# 7_can_rc_i2c_analog.net
KiCad netlist of a schematic drawn in Altium Designer
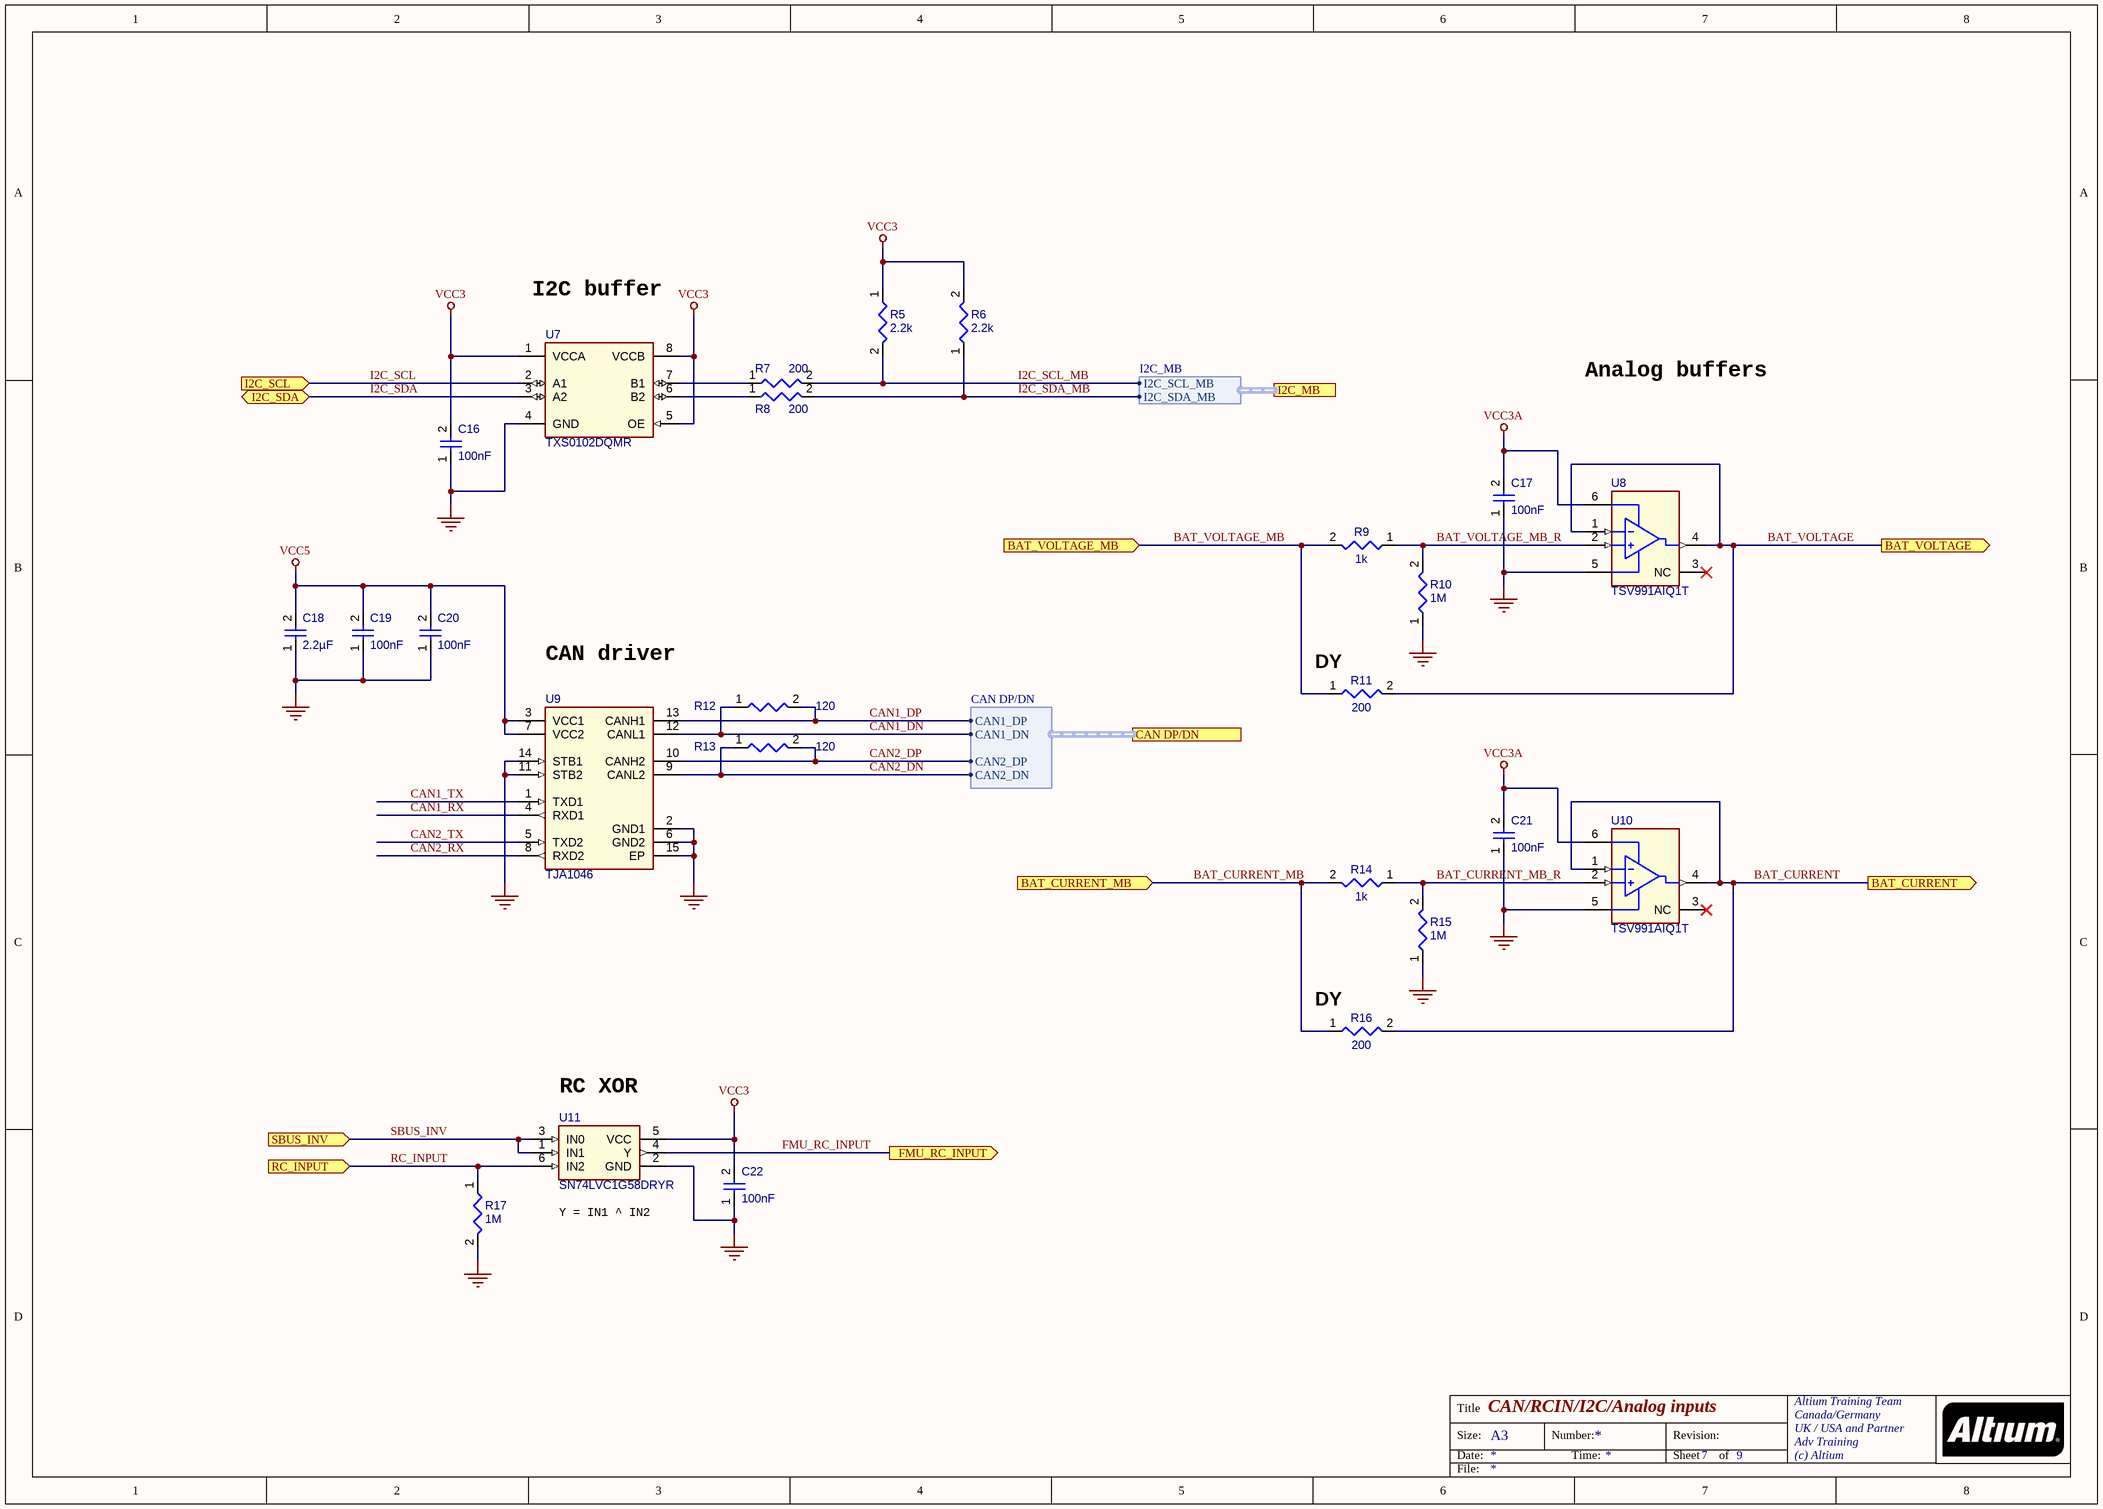
[diagram p0: 7_can_rc_i2c_analog.SchDoc]

(export (version "E")
  (design (tool "Eeschema 10.0.6"))
  (components
    (comp (ref "C16")
      (value "100nF")
      (footprint "CAPC0402(1005)60_L")
      (description "Chip Capacitor, 100nF +/-20%, 10V, 0402, Thickness 0.6 mm")
      (fields (field (name "TOLERANCE") "20%") (field (name "Comment") "Capacitor 100nF +/-20% 10V 0402"))
      (libsource (lib "<Company> Server") (part "CAP-NP-2"))
    )
    (comp (ref "C17")
      (value "100nF")
      (footprint "CAPC0402(1005)60_L")
      (description "Chip Capacitor, 100nF +/-20%, 10V, 0402, Thickness 0.6 mm")
      (fields (field (name "TOLERANCE") "20%") (field (name "Comment") "Capacitor 100nF +/-20% 10V 0402"))
      (libsource (lib "<Company> Server") (part "CAP-NP-2"))
    )
    (comp (ref "C18")
      (value "2.2µF")
      (footprint "CAPC0402(1005)60_L")
      (description "Chip Capacitor, 2,2µF +/-20%, 10V, 0402, Thickness 0.6 mm")
      (fields (field (name "TOLERANCE") "10%") (field (name "Comment") "Capacitor 2,2µF +/-20% 10V 0402"))
      (libsource (lib "<Company> Server") (part "CAP-NP-2"))
    )
    (comp (ref "C19")
      (value "100nF")
      (footprint "CAPC0402(1005)60_L")
      (description "Chip Capacitor, 100nF +/-20%, 10V, 0402, Thickness 0.6 mm")
      (fields (field (name "TOLERANCE") "20%") (field (name "Comment") "Capacitor 100nF +/-20% 10V 0402"))
      (libsource (lib "<Company> Server") (part "CAP-NP-2"))
    )
    (comp (ref "C20")
      (value "100nF")
      (footprint "CAPC0402(1005)60_L")
      (description "Chip Capacitor, 100nF +/-20%, 10V, 0402, Thickness 0.6 mm")
      (fields (field (name "TOLERANCE") "20%") (field (name "Comment") "Capacitor 100nF +/-20% 10V 0402"))
      (libsource (lib "<Company> Server") (part "CAP-NP-2"))
    )
    (comp (ref "C21")
      (value "100nF")
      (footprint "CAPC0402(1005)60_L")
      (description "Chip Capacitor, 100nF +/-20%, 10V, 0402, Thickness 0.6 mm")
      (fields (field (name "TOLERANCE") "20%") (field (name "Comment") "Capacitor 100nF +/-20% 10V 0402"))
      (libsource (lib "<Company> Server") (part "CAP-NP-2"))
    )
    (comp (ref "C22")
      (value "100nF")
      (footprint "CAPC0402(1005)60_L")
      (description "Chip Capacitor, 100nF +/-20%, 10V, 0402, Thickness 0.6 mm")
      (fields (field (name "TOLERANCE") "20%") (field (name "Comment") "Capacitor 100nF +/-20% 10V 0402"))
      (libsource (lib "<Company> Server") (part "CAP-NP-2"))
    )
    (comp (ref "R5")
      (value "2.2k")
      (footprint "RESC0402(1005)_L")
      (description "Chip Resistor, 2,2 kOhms, +/-5 %, 63 mW, -55 to 155 degC, 0402")
      (fields (field (name "POWER") "63mW") (field (name "TOLERANCE") "5%"))
      (libsource (lib "<Company> Server") (part "RES-2"))
    )
    (comp (ref "R6")
      (value "2.2k")
      (footprint "RESC0402(1005)_L")
      (description "Chip Resistor, 2,2 kOhms, +/-5 %, 63 mW, -55 to 155 degC, 0402")
      (fields (field (name "POWER") "63mW") (field (name "TOLERANCE") "5%"))
      (libsource (lib "<Company> Server") (part "RES-2"))
    )
    (comp (ref "R7")
      (value "200")
      (footprint "RESC0402(1005)_L")
      (description "Chip Resistor, 200 Ohms, +/-5 %, 63 mW, -55 to 155 degC, 0402")
      (fields (field (name "POWER") "63mW") (field (name "TOLERANCE") "5%"))
      (libsource (lib "<Company> Server") (part "RES-2"))
    )
    (comp (ref "R8")
      (value "200")
      (footprint "RESC0402(1005)_L")
      (description "Chip Resistor, 200 Ohms, +/-5 %, 63 mW, -55 to 155 degC, 0402")
      (fields (field (name "POWER") "63mW") (field (name "TOLERANCE") "5%"))
      (libsource (lib "<Company> Server") (part "RES-2"))
    )
    (comp (ref "R9")
      (value "1k")
      (footprint "RESC0402(1005)_L")
      (description "Chip Resistor, 1 kOhms, +/-5 %, 63 mW, -55 to 155 degC, 0402")
      (fields (field (name "TOLERANCE") "5%") (field (name "POWER") "63mW"))
      (libsource (lib "<Company> Server") (part "RES-2"))
    )
    (comp (ref "R10")
      (value "1M")
      (footprint "RESC0402(1005)_L")
      (description "Chip Resistor, 1 MOhms, +/-5 %, 63 mW, -55 to 155 degC, 0402")
      (fields (field (name "TOLERANCE") "5%") (field (name "POWER") "63mW"))
      (libsource (lib "<Company> Server") (part "RES-2"))
    )
    (comp (ref "R11")
      (value "200")
      (footprint "RESC0402(1005)_L")
      (description "Chip Resistor, 200 Ohms, +/-5 %, 63 mW, -55 to 155 degC, 0402")
      (fields (field (name "POWER") "63mW") (field (name "TOLERANCE") "5%"))
      (libsource (lib "<Company> Server") (part "RES-2"))
    )
    (comp (ref "R12")
      (value "120")
      (footprint "RESC0603(1608)_L")
      (description "Chip Resistor, 120 Ohms, +/-5 %, 0.1 W, -55 to 155 degC, 0603")
      (fields (field (name "TOLERANCE") "5%") (field (name "POWER") "100mW"))
      (libsource (lib "<Company> Server") (part "RES-2"))
    )
    (comp (ref "R13")
      (value "120")
      (footprint "RESC0603(1608)_L")
      (description "Chip Resistor, 120 Ohms, +/-5 %, 0.1 W, -55 to 155 degC, 0603")
      (fields (field (name "TOLERANCE") "5%") (field (name "POWER") "100mW"))
      (libsource (lib "<Company> Server") (part "RES-2"))
    )
    (comp (ref "R14")
      (value "1k")
      (footprint "RESC0402(1005)_L")
      (description "Chip Resistor, 1 kOhms, +/-5 %, 63 mW, -55 to 155 degC, 0402")
      (fields (field (name "TOLERANCE") "5%") (field (name "POWER") "63mW"))
      (libsource (lib "<Company> Server") (part "RES-2"))
    )
    (comp (ref "R15")
      (value "1M")
      (footprint "RESC0402(1005)_L")
      (description "Chip Resistor, 1 MOhms, +/-5 %, 63 mW, -55 to 155 degC, 0402")
      (fields (field (name "TOLERANCE") "5%") (field (name "POWER") "63mW"))
      (libsource (lib "<Company> Server") (part "RES-2"))
    )
    (comp (ref "R16")
      (value "200")
      (footprint "RESC0402(1005)_L")
      (description "Chip Resistor, 200 Ohms, +/-5 %, 63 mW, -55 to 155 degC, 0402")
      (fields (field (name "POWER") "63mW") (field (name "TOLERANCE") "5%"))
      (libsource (lib "<Company> Server") (part "RES-2"))
    )
    (comp (ref "R17")
      (value "1M")
      (footprint "RESC0402(1005)_L")
      (description "Chip Resistor, 1 MOhms, +/-5 %, 63 mW, -55 to 155 degC, 0402")
      (fields (field (name "TOLERANCE") "5%") (field (name "POWER") "63mW"))
      (libsource (lib "<Company> Server") (part "RES-2"))
    )
    (comp (ref "U7")
      (value "TXS0102DQMR")
      (footprint "DQM")
      (description "IC TRANSLATOR VOLTAGE 8-X2SON")
      (libsource (lib "<Company> Server") (part "CMP-001-0022-1"))
    )
    (comp (ref "U8")
      (value "TSV991AIQ1T")
      (footprint "STM-DFN-8_V")
      (libsource (lib "<Company> Server") (part "CMP-001-0008-5"))
    )
    (comp (ref "U9")
      (value "TJA1046")
      (footprint "NXP-SOT1086-2_L")
      (libsource (lib "<Company> Server") (part "CMP-00180-5"))
    )
    (comp (ref "U10")
      (value "TSV991AIQ1T")
      (footprint "STM-DFN-8_V")
      (libsource (lib "<Company> Server") (part "CMP-001-0008-5"))
    )
    (comp (ref "U11")
      (value "SN74LVC1G58DRYR")
      (footprint "DRY0006A_V")
      (description "CONFIGURABLE MULTIPLE-FUNCTION GATE, DRY0006A, LARGE T&R")
      (libsource (lib "<Company> Server") (part "CMP-00132-5"))
    )
  )
  (nets
    (net (code "4") (name "/BAT_CURRENT") (class "Default")
      (node (ref "R16") (pin "2") (pinfunction "2_2") (pintype "passive"))
      (node (ref "U10") (pin "1") (pinfunction "IN-_1") (pintype "input"))
      (node (ref "U10") (pin "4") (pinfunction "OUT_4") (pintype "output"))
    )
    (net (code "5") (name "/BAT_CURRENT_MB") (class "Default")
      (node (ref "R14") (pin "2") (pinfunction "2_2") (pintype "passive"))
      (node (ref "R16") (pin "1") (pinfunction "1_1") (pintype "passive"))
    )
    (net (code "6") (name "/BAT_CURRENT_MB_R") (class "Default")
      (node (ref "R14") (pin "1") (pinfunction "1_1") (pintype "passive"))
      (node (ref "R15") (pin "2") (pinfunction "2_2") (pintype "passive"))
      (node (ref "U10") (pin "2") (pinfunction "IN+_2") (pintype "input"))
    )
    (net (code "7") (name "/BAT_VOLTAGE") (class "Default")
      (node (ref "R11") (pin "2") (pinfunction "2_2") (pintype "passive"))
      (node (ref "U8") (pin "1") (pinfunction "IN-_1") (pintype "input"))
      (node (ref "U8") (pin "4") (pinfunction "OUT_4") (pintype "output"))
    )
    (net (code "8") (name "/BAT_VOLTAGE_MB") (class "Default")
      (node (ref "R11") (pin "1") (pinfunction "1_1") (pintype "passive"))
      (node (ref "R9") (pin "2") (pinfunction "2_2") (pintype "passive"))
    )
    (net (code "9") (name "/BAT_VOLTAGE_MB_R") (class "Default")
      (node (ref "R10") (pin "2") (pinfunction "2_2") (pintype "passive"))
      (node (ref "R9") (pin "1") (pinfunction "1_1") (pintype "passive"))
      (node (ref "U8") (pin "2") (pinfunction "IN+_2") (pintype "input"))
    )
    (net (code "10") (name "/CAN1_DN") (class "Default")
      (node (ref "R12") (pin "1") (pinfunction "1_1") (pintype "passive"))
      (node (ref "U9") (pin "12") (pinfunction "CANL1_12") (pintype "passive"))
    )
    (net (code "11") (name "/CAN1_DP") (class "Default")
      (node (ref "R12") (pin "2") (pinfunction "2_2") (pintype "passive"))
      (node (ref "U9") (pin "13") (pinfunction "CANH1_13") (pintype "passive"))
    )
    (net (code "12") (name "/CAN1_RX") (class "Default")
      (node (ref "U9") (pin "4") (pinfunction "RXD1_4") (pintype "output"))
    )
    (net (code "13") (name "/CAN1_TX") (class "Default")
      (node (ref "U9") (pin "1") (pinfunction "TXD1_1") (pintype "input"))
    )
    (net (code "14") (name "/CAN2_DN") (class "Default")
      (node (ref "R13") (pin "1") (pinfunction "1_1") (pintype "passive"))
      (node (ref "U9") (pin "9") (pinfunction "CANL2_9") (pintype "passive"))
    )
    (net (code "15") (name "/CAN2_DP") (class "Default")
      (node (ref "R13") (pin "2") (pinfunction "2_2") (pintype "passive"))
      (node (ref "U9") (pin "10") (pinfunction "CANH2_10") (pintype "passive"))
    )
    (net (code "16") (name "/CAN2_RX") (class "Default")
      (node (ref "U9") (pin "8") (pinfunction "RXD2_8") (pintype "output"))
    )
    (net (code "17") (name "/CAN2_TX") (class "Default")
      (node (ref "U9") (pin "5") (pinfunction "TXD2_5") (pintype "input"))
    )
    (net (code "18") (name "/FMU_RC_INPUT") (class "Default")
      (node (ref "U11") (pin "4") (pinfunction "Y_4") (pintype "output"))
    )
    (net (code "19") (name "/I2C_SCL") (class "Default")
      (node (ref "U7") (pin "2") (pinfunction "A1_2") (pintype "bidirectional"))
    )
    (net (code "20") (name "/I2C_SCL_MB") (class "Default")
      (node (ref "R5") (pin "2") (pinfunction "2_2") (pintype "passive"))
      (node (ref "R7") (pin "2") (pinfunction "2_2") (pintype "passive"))
    )
    (net (code "21") (name "/I2C_SDA") (class "Default")
      (node (ref "U7") (pin "3") (pinfunction "A2_3") (pintype "bidirectional"))
    )
    (net (code "22") (name "/I2C_SDA_MB") (class "Default")
      (node (ref "R6") (pin "1") (pinfunction "1_1") (pintype "passive"))
      (node (ref "R8") (pin "2") (pinfunction "2_2") (pintype "passive"))
    )
    (net (code "23") (name "/RC_INPUT") (class "Default")
      (node (ref "R17") (pin "1") (pinfunction "1_1") (pintype "passive"))
      (node (ref "U11") (pin "6") (pinfunction "IN2_6") (pintype "input"))
    )
    (net (code "24") (name "/SBUS_INV") (class "Default")
      (node (ref "U11") (pin "1") (pinfunction "IN1_1") (pintype "input"))
      (node (ref "U11") (pin "3") (pinfunction "IN0_3") (pintype "input"))
    )
    (net (code "27") (name "GND") (class "Default")
      (node (ref "C16") (pin "1") (pinfunction "1_1") (pintype "passive"))
      (node (ref "C17") (pin "1") (pinfunction "1_1") (pintype "passive"))
      (node (ref "C18") (pin "1") (pinfunction "1_1") (pintype "passive"))
      (node (ref "C19") (pin "1") (pinfunction "1_1") (pintype "passive"))
      (node (ref "C20") (pin "1") (pinfunction "1_1") (pintype "passive"))
      (node (ref "C21") (pin "1") (pinfunction "1_1") (pintype "passive"))
      (node (ref "C22") (pin "1") (pinfunction "1_1") (pintype "passive"))
      (node (ref "R10") (pin "1") (pinfunction "1_1") (pintype "passive"))
      (node (ref "R15") (pin "1") (pinfunction "1_1") (pintype "passive"))
      (node (ref "R17") (pin "2") (pinfunction "2_2") (pintype "passive"))
      (node (ref "U10") (pin "5") (pinfunction "VCC-_5") (pintype "power_in"))
      (node (ref "U11") (pin "2") (pinfunction "GND_2") (pintype "power_in"))
      (node (ref "U7") (pin "4") (pinfunction "GND_4") (pintype "power_in"))
      (node (ref "U8") (pin "5") (pinfunction "VCC-_5") (pintype "power_in"))
      (node (ref "U9") (pin "11") (pinfunction "STB2_11") (pintype "input"))
      (node (ref "U9") (pin "14") (pinfunction "STB1_14") (pintype "input"))
      (node (ref "U9") (pin "15") (pinfunction "EP_15") (pintype "power_in"))
      (node (ref "U9") (pin "2") (pinfunction "GND1_2") (pintype "power_in"))
      (node (ref "U9") (pin "6") (pinfunction "GND2_6") (pintype "power_in"))
    )
    (net (code "28") (name "Net-(U7-B1)") (class "Default")
      (node (ref "R7") (pin "1") (pinfunction "1_1") (pintype "passive"))
      (node (ref "U7") (pin "7") (pinfunction "B1_7") (pintype "bidirectional"))
    )
    (net (code "29") (name "Net-(U7-B2)") (class "Default")
      (node (ref "R8") (pin "1") (pinfunction "1_1") (pintype "passive"))
      (node (ref "U7") (pin "6") (pinfunction "B2_6") (pintype "bidirectional"))
    )
    (net (code "30") (name "VCC3") (class "Default")
      (node (ref "C16") (pin "2") (pinfunction "2_2") (pintype "passive"))
      (node (ref "C22") (pin "2") (pinfunction "2_2") (pintype "passive"))
      (node (ref "R5") (pin "1") (pinfunction "1_1") (pintype "passive"))
      (node (ref "R6") (pin "2") (pinfunction "2_2") (pintype "passive"))
      (node (ref "U11") (pin "5") (pinfunction "VCC_5") (pintype "power_in"))
      (node (ref "U7") (pin "1") (pinfunction "VCCA_1") (pintype "power_in"))
      (node (ref "U7") (pin "5") (pinfunction "OE_5") (pintype "input"))
      (node (ref "U7") (pin "8") (pinfunction "VCCB_8") (pintype "power_in"))
    )
    (net (code "31") (name "VCC3A") (class "Default")
      (node (ref "C17") (pin "2") (pinfunction "2_2") (pintype "passive"))
      (node (ref "C21") (pin "2") (pinfunction "2_2") (pintype "passive"))
      (node (ref "U10") (pin "6") (pinfunction "VCC+_6") (pintype "power_in"))
      (node (ref "U8") (pin "6") (pinfunction "VCC+_6") (pintype "power_in"))
    )
    (net (code "32") (name "VCC5") (class "Default")
      (node (ref "C18") (pin "2") (pinfunction "2_2") (pintype "passive"))
      (node (ref "C19") (pin "2") (pinfunction "2_2") (pintype "passive"))
      (node (ref "C20") (pin "2") (pinfunction "2_2") (pintype "passive"))
      (node (ref "U9") (pin "3") (pinfunction "VCC1_3") (pintype "power_in"))
      (node (ref "U9") (pin "7") (pinfunction "VCC2_7") (pintype "power_in"))
    )
    (net (code "33") (name "unconnected-(U8-NC-Pad3)") (class "Default")
      (node (ref "U8") (pin "3") (pinfunction "NC_3") (pintype "passive+no_connect"))
    )
    (net (code "34") (name "unconnected-(U10-NC-Pad3)") (class "Default")
      (node (ref "U10") (pin "3") (pinfunction "NC_3") (pintype "passive+no_connect"))
    )
  )
)
